# T09_LockBox-Schematic_ver4_sch.net
KiCad netlist of a schematic drawn in EAGLE
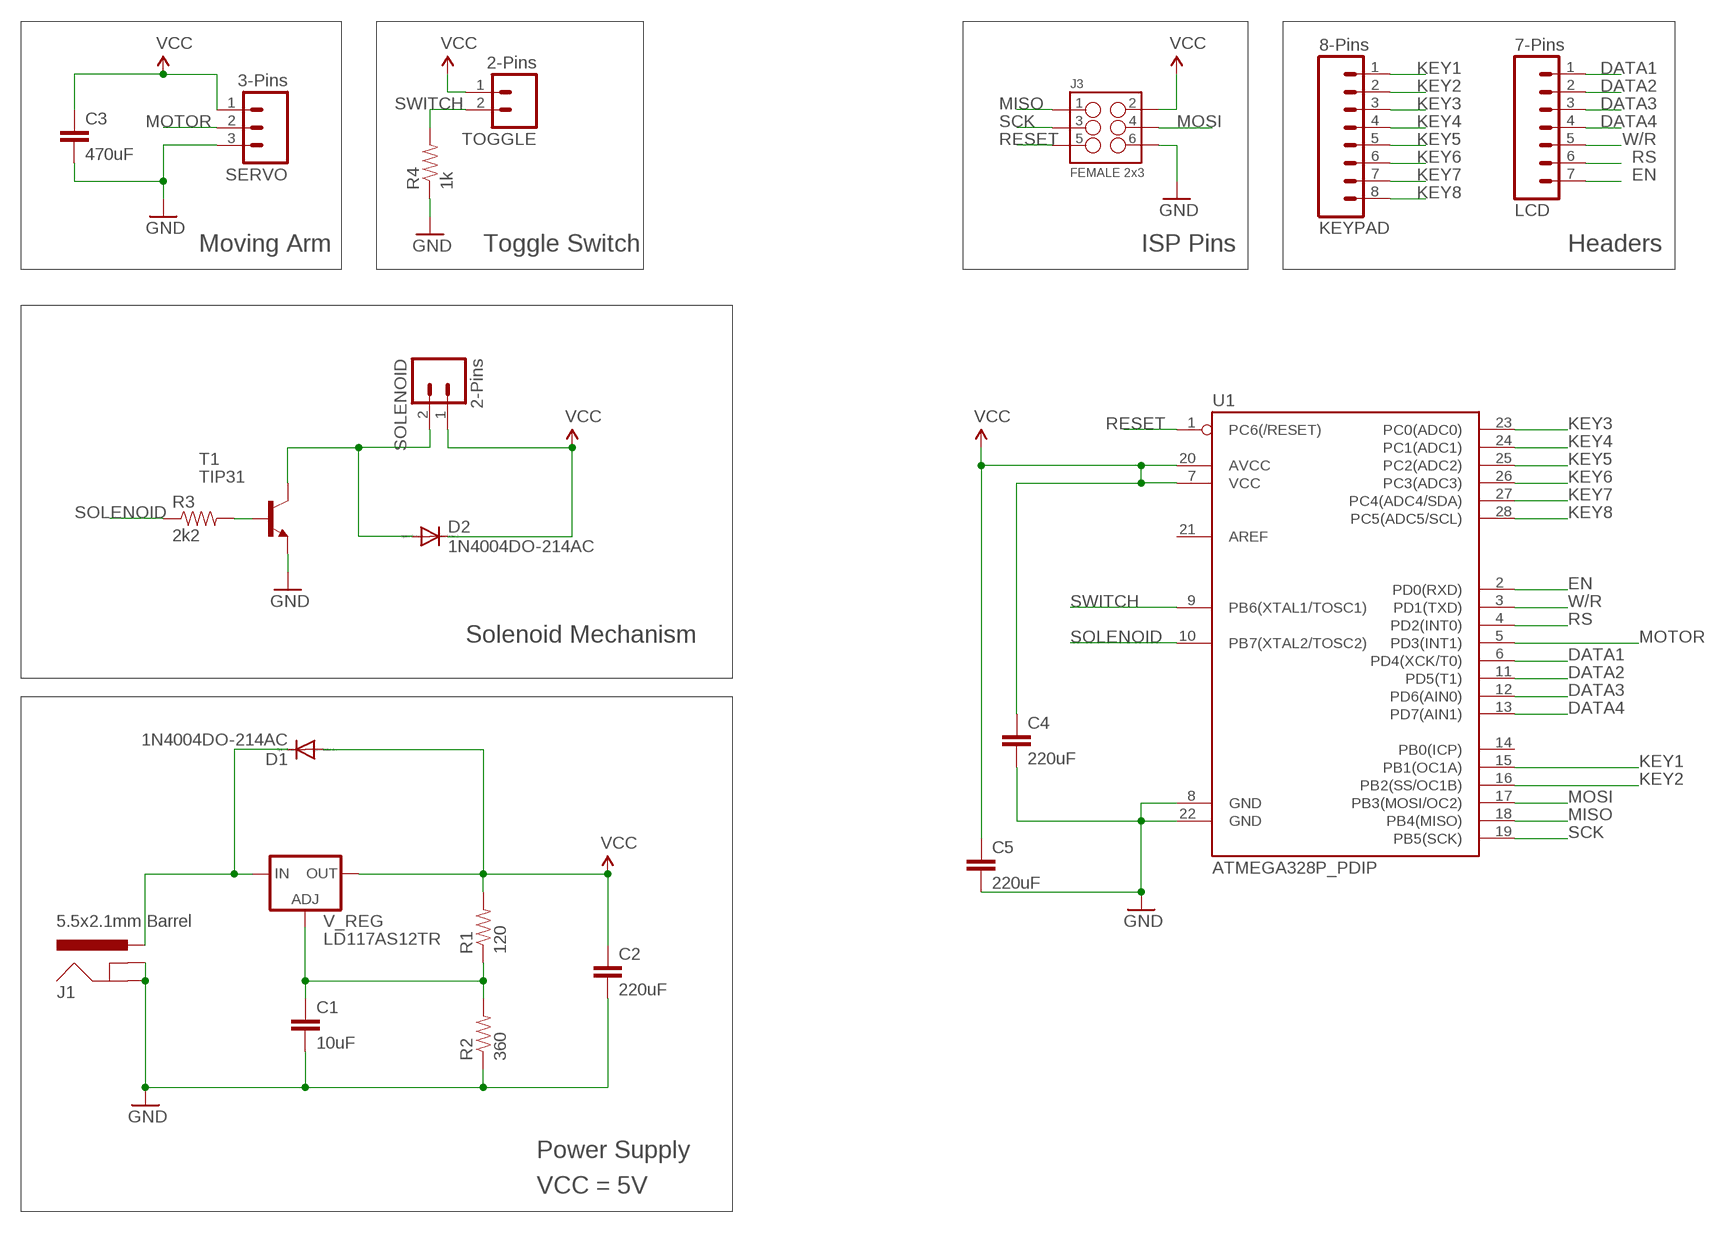
[diagram p0: schematic, sheet 1]

(export (version "E")
  (design (tool "Eeschema 10.0.6"))
  (components
    (comp (ref "C1")
      (value "10uF")
      (footprint "eagle-import:0603-CAP")
      (libsource (lib "eagle-import") (part "SparkFun-Passives_CAP0603-CAP"))
    )
    (comp (ref "C2")
      (value "220uF")
      (footprint "eagle-import:0603-CAP")
      (libsource (lib "eagle-import") (part "SparkFun-Passives_CAP0603-CAP"))
    )
    (comp (ref "C3")
      (value "470uF")
      (footprint "eagle-import:0603-CAP")
      (libsource (lib "eagle-import") (part "CAP0603-CAP"))
    )
    (comp (ref "C4")
      (value "220uF")
      (footprint "eagle-import:0603-CAP")
      (libsource (lib "eagle-import") (part "SparkFun-Passives_CAP0603-CAP"))
    )
    (comp (ref "C5")
      (value "220uF")
      (footprint "eagle-import:0603-CAP")
      (libsource (lib "eagle-import") (part "SparkFun-Passives_CAP0603-CAP"))
    )
    (comp (ref "D1")
      (value "1N4004DO-214AC")
      (footprint "eagle-import:DO-214AC")
      (libsource (lib "eagle-import") (part "1N4004DO-214AC"))
    )
    (comp (ref "D2")
      (value "1N4004DO-214AC")
      (footprint "eagle-import:DO-214AC")
      (libsource (lib "eagle-import") (part "1N4004DO-214AC"))
    )
    (comp (ref "J1")
      (value "5.5x2.1mm Barrel")
      (footprint "eagle-import:POWER_JACK_SMD")
      (libsource (lib "eagle-import") (part "POWER_JACKSMD"))
    )
    (comp (ref "J3")
      (value "FEMALE 2x3")
      (footprint "eagle-import:2X3")
      (libsource (lib "eagle-import") (part "M03X2FEMALE"))
    )
    (comp (ref "KEYPAD")
      (value "8-Pins")
      (footprint "eagle-import:1X08_ROUND")
      (libsource (lib "eagle-import") (part "M08"))
    )
    (comp (ref "LCD")
      (value "7-Pins")
      (footprint "eagle-import:1X07")
      (libsource (lib "eagle-import") (part "M07"))
    )
    (comp (ref "R1")
      (value "120")
      (footprint "eagle-import:0603-RES")
      (libsource (lib "eagle-import") (part "RESISTOR0603"))
    )
    (comp (ref "R2")
      (value "360")
      (footprint "eagle-import:0603-RES")
      (libsource (lib "eagle-import") (part "RESISTOR0603"))
    )
    (comp (ref "R3")
      (value "2k2")
      (footprint "eagle-import:0603-RES")
      (libsource (lib "eagle-import") (part "RESISTOR0603"))
    )
    (comp (ref "R4")
      (value "1k")
      (footprint "eagle-import:0603-RES")
      (libsource (lib "eagle-import") (part "RESISTOR0603"))
    )
    (comp (ref "SERVO")
      (value "3-Pins")
      (footprint "eagle-import:1X03")
      (libsource (lib "eagle-import") (part "M03PTH"))
    )
    (comp (ref "SOLENOID")
      (value "2-Pins")
      (footprint "eagle-import:1X02")
      (libsource (lib "eagle-import") (part "M02PTH"))
    )
    (comp (ref "T1")
      (value "TIP31")
      (footprint "eagle-import:TO220")
      (libsource (lib "eagle-import") (part "TIP31"))
    )
    (comp (ref "TOGGLE")
      (value "2-Pins")
      (footprint "eagle-import:1X02")
      (libsource (lib "eagle-import") (part "M02PTH"))
    )
    (comp (ref "U1")
      (value "ATMEGA328P_PDIP")
      (footprint "eagle-import:DIL28-3")
      (libsource (lib "eagle-import") (part "ATMEGA328P_PDIP"))
    )
    (comp (ref "V_REG")
      (value "LD117AS12TR")
      (footprint "eagle-import:SOT223")
      (libsource (lib "eagle-import") (part "LD117A?S12TR"))
    )
  )
  (nets
    (net (code "1") (name "/DATA1") (class "Default")
      (node (ref "LCD") (pin "1") (pinfunction "1_1") (pintype "passive"))
      (node (ref "U1") (pin "6") (pinfunction "PD4(XCK/T0)_6") (pintype "bidirectional"))
    )
    (net (code "2") (name "/DATA2") (class "Default")
      (node (ref "LCD") (pin "2") (pinfunction "2_2") (pintype "passive"))
      (node (ref "U1") (pin "11") (pinfunction "PD5(T1)_11") (pintype "bidirectional"))
    )
    (net (code "3") (name "/DATA3") (class "Default")
      (node (ref "LCD") (pin "3") (pinfunction "3_3") (pintype "passive"))
      (node (ref "U1") (pin "12") (pinfunction "PD6(AIN0)_12") (pintype "bidirectional"))
    )
    (net (code "4") (name "/DATA4") (class "Default")
      (node (ref "LCD") (pin "4") (pinfunction "4_4") (pintype "passive"))
      (node (ref "U1") (pin "13") (pinfunction "PD7(AIN1)_13") (pintype "bidirectional"))
    )
    (net (code "5") (name "/EN") (class "Default")
      (node (ref "LCD") (pin "7") (pinfunction "7_7") (pintype "passive"))
      (node (ref "U1") (pin "2") (pinfunction "PD0(RXD)_2") (pintype "bidirectional"))
    )
    (net (code "6") (name "/KEY1") (class "Default")
      (node (ref "KEYPAD") (pin "1") (pinfunction "1_1") (pintype "passive"))
      (node (ref "U1") (pin "15") (pinfunction "PB1(OC1A)_15") (pintype "bidirectional"))
    )
    (net (code "7") (name "/KEY2") (class "Default")
      (node (ref "KEYPAD") (pin "2") (pinfunction "2_2") (pintype "passive"))
      (node (ref "U1") (pin "16") (pinfunction "PB2(SS/OC1B)_16") (pintype "bidirectional"))
    )
    (net (code "8") (name "/KEY3") (class "Default")
      (node (ref "KEYPAD") (pin "3") (pinfunction "3_3") (pintype "passive"))
      (node (ref "U1") (pin "23") (pinfunction "PC0(ADC0)_23") (pintype "bidirectional"))
    )
    (net (code "9") (name "/KEY4") (class "Default")
      (node (ref "KEYPAD") (pin "4") (pinfunction "4_4") (pintype "passive"))
      (node (ref "U1") (pin "24") (pinfunction "PC1(ADC1)_24") (pintype "bidirectional"))
    )
    (net (code "10") (name "/KEY5") (class "Default")
      (node (ref "KEYPAD") (pin "5") (pinfunction "5_5") (pintype "passive"))
      (node (ref "U1") (pin "25") (pinfunction "PC2(ADC2)_25") (pintype "bidirectional"))
    )
    (net (code "11") (name "/KEY6") (class "Default")
      (node (ref "KEYPAD") (pin "6") (pinfunction "6_6") (pintype "passive"))
      (node (ref "U1") (pin "26") (pinfunction "PC3(ADC3)_26") (pintype "bidirectional"))
    )
    (net (code "12") (name "/KEY7") (class "Default")
      (node (ref "KEYPAD") (pin "7") (pinfunction "7_7") (pintype "passive"))
      (node (ref "U1") (pin "27") (pinfunction "PC4(ADC4/SDA)_27") (pintype "bidirectional"))
    )
    (net (code "13") (name "/KEY8") (class "Default")
      (node (ref "KEYPAD") (pin "8") (pinfunction "8_8") (pintype "passive"))
      (node (ref "U1") (pin "28") (pinfunction "PC5(ADC5/SCL)_28") (pintype "bidirectional"))
    )
    (net (code "14") (name "/MISO") (class "Default")
      (node (ref "J3") (pin "1") (pinfunction "1_1") (pintype "bidirectional"))
      (node (ref "U1") (pin "18") (pinfunction "PB4(MISO)_18") (pintype "bidirectional"))
    )
    (net (code "15") (name "/MOSI") (class "Default")
      (node (ref "J3") (pin "4") (pinfunction "4_4") (pintype "bidirectional"))
      (node (ref "U1") (pin "17") (pinfunction "PB3(MOSI/OC2)_17") (pintype "bidirectional"))
    )
    (net (code "16") (name "/MOTOR") (class "Default")
      (node (ref "SERVO") (pin "2") (pinfunction "2_2") (pintype "passive"))
      (node (ref "U1") (pin "5") (pinfunction "PD3(INT1)_5") (pintype "bidirectional"))
    )
    (net (code "17") (name "/RESET") (class "Default")
      (node (ref "J3") (pin "5") (pinfunction "5_5") (pintype "bidirectional"))
      (node (ref "U1") (pin "1") (pinfunction "PC6(/RESET)_1") (pintype "bidirectional"))
    )
    (net (code "18") (name "/RS") (class "Default")
      (node (ref "LCD") (pin "6") (pinfunction "6_6") (pintype "passive"))
      (node (ref "U1") (pin "4") (pinfunction "PD2(INT0)_4") (pintype "bidirectional"))
    )
    (net (code "19") (name "/SCK") (class "Default")
      (node (ref "J3") (pin "3") (pinfunction "3_3") (pintype "bidirectional"))
      (node (ref "U1") (pin "19") (pinfunction "PB5(SCK)_19") (pintype "bidirectional"))
    )
    (net (code "20") (name "/SOLENOID") (class "Default")
      (node (ref "R3") (pin "1") (pinfunction "1_1") (pintype "passive"))
      (node (ref "U1") (pin "10") (pinfunction "PB7(XTAL2/TOSC2)_10") (pintype "bidirectional"))
    )
    (net (code "21") (name "/SWITCH") (class "Default")
      (node (ref "R4") (pin "2") (pinfunction "2_2") (pintype "passive"))
      (node (ref "TOGGLE") (pin "2") (pinfunction "2_2") (pintype "passive"))
      (node (ref "U1") (pin "9") (pinfunction "PB6(XTAL1/TOSC1)_9") (pintype "bidirectional"))
    )
    (net (code "22") (name "/W{slash}R") (class "Default")
      (node (ref "LCD") (pin "5") (pinfunction "5_5") (pintype "passive"))
      (node (ref "U1") (pin "3") (pinfunction "PD1(TXD)_3") (pintype "bidirectional"))
    )
    (net (code "23") (name "GND") (class "Default")
      (node (ref "C1") (pin "2") (pinfunction "2_2") (pintype "passive"))
      (node (ref "C2") (pin "2") (pinfunction "2_2") (pintype "passive"))
      (node (ref "C3") (pin "2") (pinfunction "2_2") (pintype "passive"))
      (node (ref "C4") (pin "2") (pinfunction "2_2") (pintype "passive"))
      (node (ref "C5") (pin "2") (pinfunction "2_2") (pintype "passive"))
      (node (ref "J1") (pin "GND") (pinfunction "GNDBREAK_GND") (pintype "bidirectional"))
      (node (ref "J1") (pin "P$4") (pinfunction "GND_P$4") (pintype "bidirectional"))
      (node (ref "J3") (pin "6") (pinfunction "6_6") (pintype "bidirectional"))
      (node (ref "R2") (pin "1") (pinfunction "1_1") (pintype "passive"))
      (node (ref "R4") (pin "1") (pinfunction "1_1") (pintype "passive"))
      (node (ref "SERVO") (pin "3") (pinfunction "3_3") (pintype "passive"))
      (node (ref "T1") (pin "3") (pinfunction "E_3") (pintype "passive"))
      (node (ref "U1") (pin "22") (pinfunction "GND_22") (pintype "bidirectional"))
      (node (ref "U1") (pin "8") (pinfunction "GND_8") (pintype "bidirectional"))
    )
    (net (code "24") (name "Net-(J1-PWR)") (class "Default")
      (node (ref "D1") (pin "C") (pinfunction "C_C") (pintype "passive"))
      (node (ref "J1") (pin "VIN0") (pinfunction "PWR_VIN0") (pintype "bidirectional"))
      (node (ref "V_REG") (pin "3") (pinfunction "IN_3") (pintype "input"))
    )
    (net (code "25") (name "Net-(T1-B)") (class "Default")
      (node (ref "R3") (pin "2") (pinfunction "2_2") (pintype "passive"))
      (node (ref "T1") (pin "1") (pinfunction "B_1") (pintype "passive"))
    )
    (net (code "26") (name "Net-(T1-C)") (class "Default")
      (node (ref "D2") (pin "A") (pinfunction "A_A") (pintype "passive"))
      (node (ref "SOLENOID") (pin "2") (pinfunction "2_2") (pintype "passive"))
      (node (ref "T1") (pin "2") (pinfunction "C_2") (pintype "passive"))
    )
    (net (code "27") (name "Net-(V_REG-ADJ)") (class "Default")
      (node (ref "C1") (pin "1") (pinfunction "1_1") (pintype "passive"))
      (node (ref "R1") (pin "1") (pinfunction "1_1") (pintype "passive"))
      (node (ref "R2") (pin "2") (pinfunction "2_2") (pintype "passive"))
      (node (ref "V_REG") (pin "1") (pinfunction "ADJ_1") (pintype "input"))
    )
    (net (code "28") (name "VCC") (class "Default")
      (node (ref "C2") (pin "1") (pinfunction "1_1") (pintype "passive"))
      (node (ref "C3") (pin "1") (pinfunction "1_1") (pintype "passive"))
      (node (ref "C4") (pin "1") (pinfunction "1_1") (pintype "passive"))
      (node (ref "C5") (pin "1") (pinfunction "1_1") (pintype "passive"))
      (node (ref "D1") (pin "A") (pinfunction "A_A") (pintype "passive"))
      (node (ref "D2") (pin "C") (pinfunction "C_C") (pintype "passive"))
      (node (ref "J3") (pin "2") (pinfunction "2_2") (pintype "bidirectional"))
      (node (ref "R1") (pin "2") (pinfunction "2_2") (pintype "passive"))
      (node (ref "SERVO") (pin "1") (pinfunction "1_1") (pintype "passive"))
      (node (ref "SOLENOID") (pin "1") (pinfunction "1_1") (pintype "passive"))
      (node (ref "TOGGLE") (pin "1") (pinfunction "1_1") (pintype "passive"))
      (node (ref "U1") (pin "20") (pinfunction "AVCC_20") (pintype "bidirectional"))
      (node (ref "U1") (pin "7") (pinfunction "VCC_7") (pintype "bidirectional"))
      (node (ref "V_REG") (pin "4") (pinfunction "OUT_4") (pintype "passive"))
    )
    (net (code "29") (name "unconnected-(U1-AREF-Pad21)") (class "Default")
      (node (ref "U1") (pin "21") (pinfunction "AREF_21") (pintype "bidirectional"))
    )
    (net (code "30") (name "unconnected-(U1-PB0(ICP)-Pad14)") (class "Default")
      (node (ref "U1") (pin "14") (pinfunction "PB0(ICP)_14") (pintype "bidirectional"))
    )
  )
)
